# 10_USB.net
KiCad netlist of a schematic drawn in Altium Designer
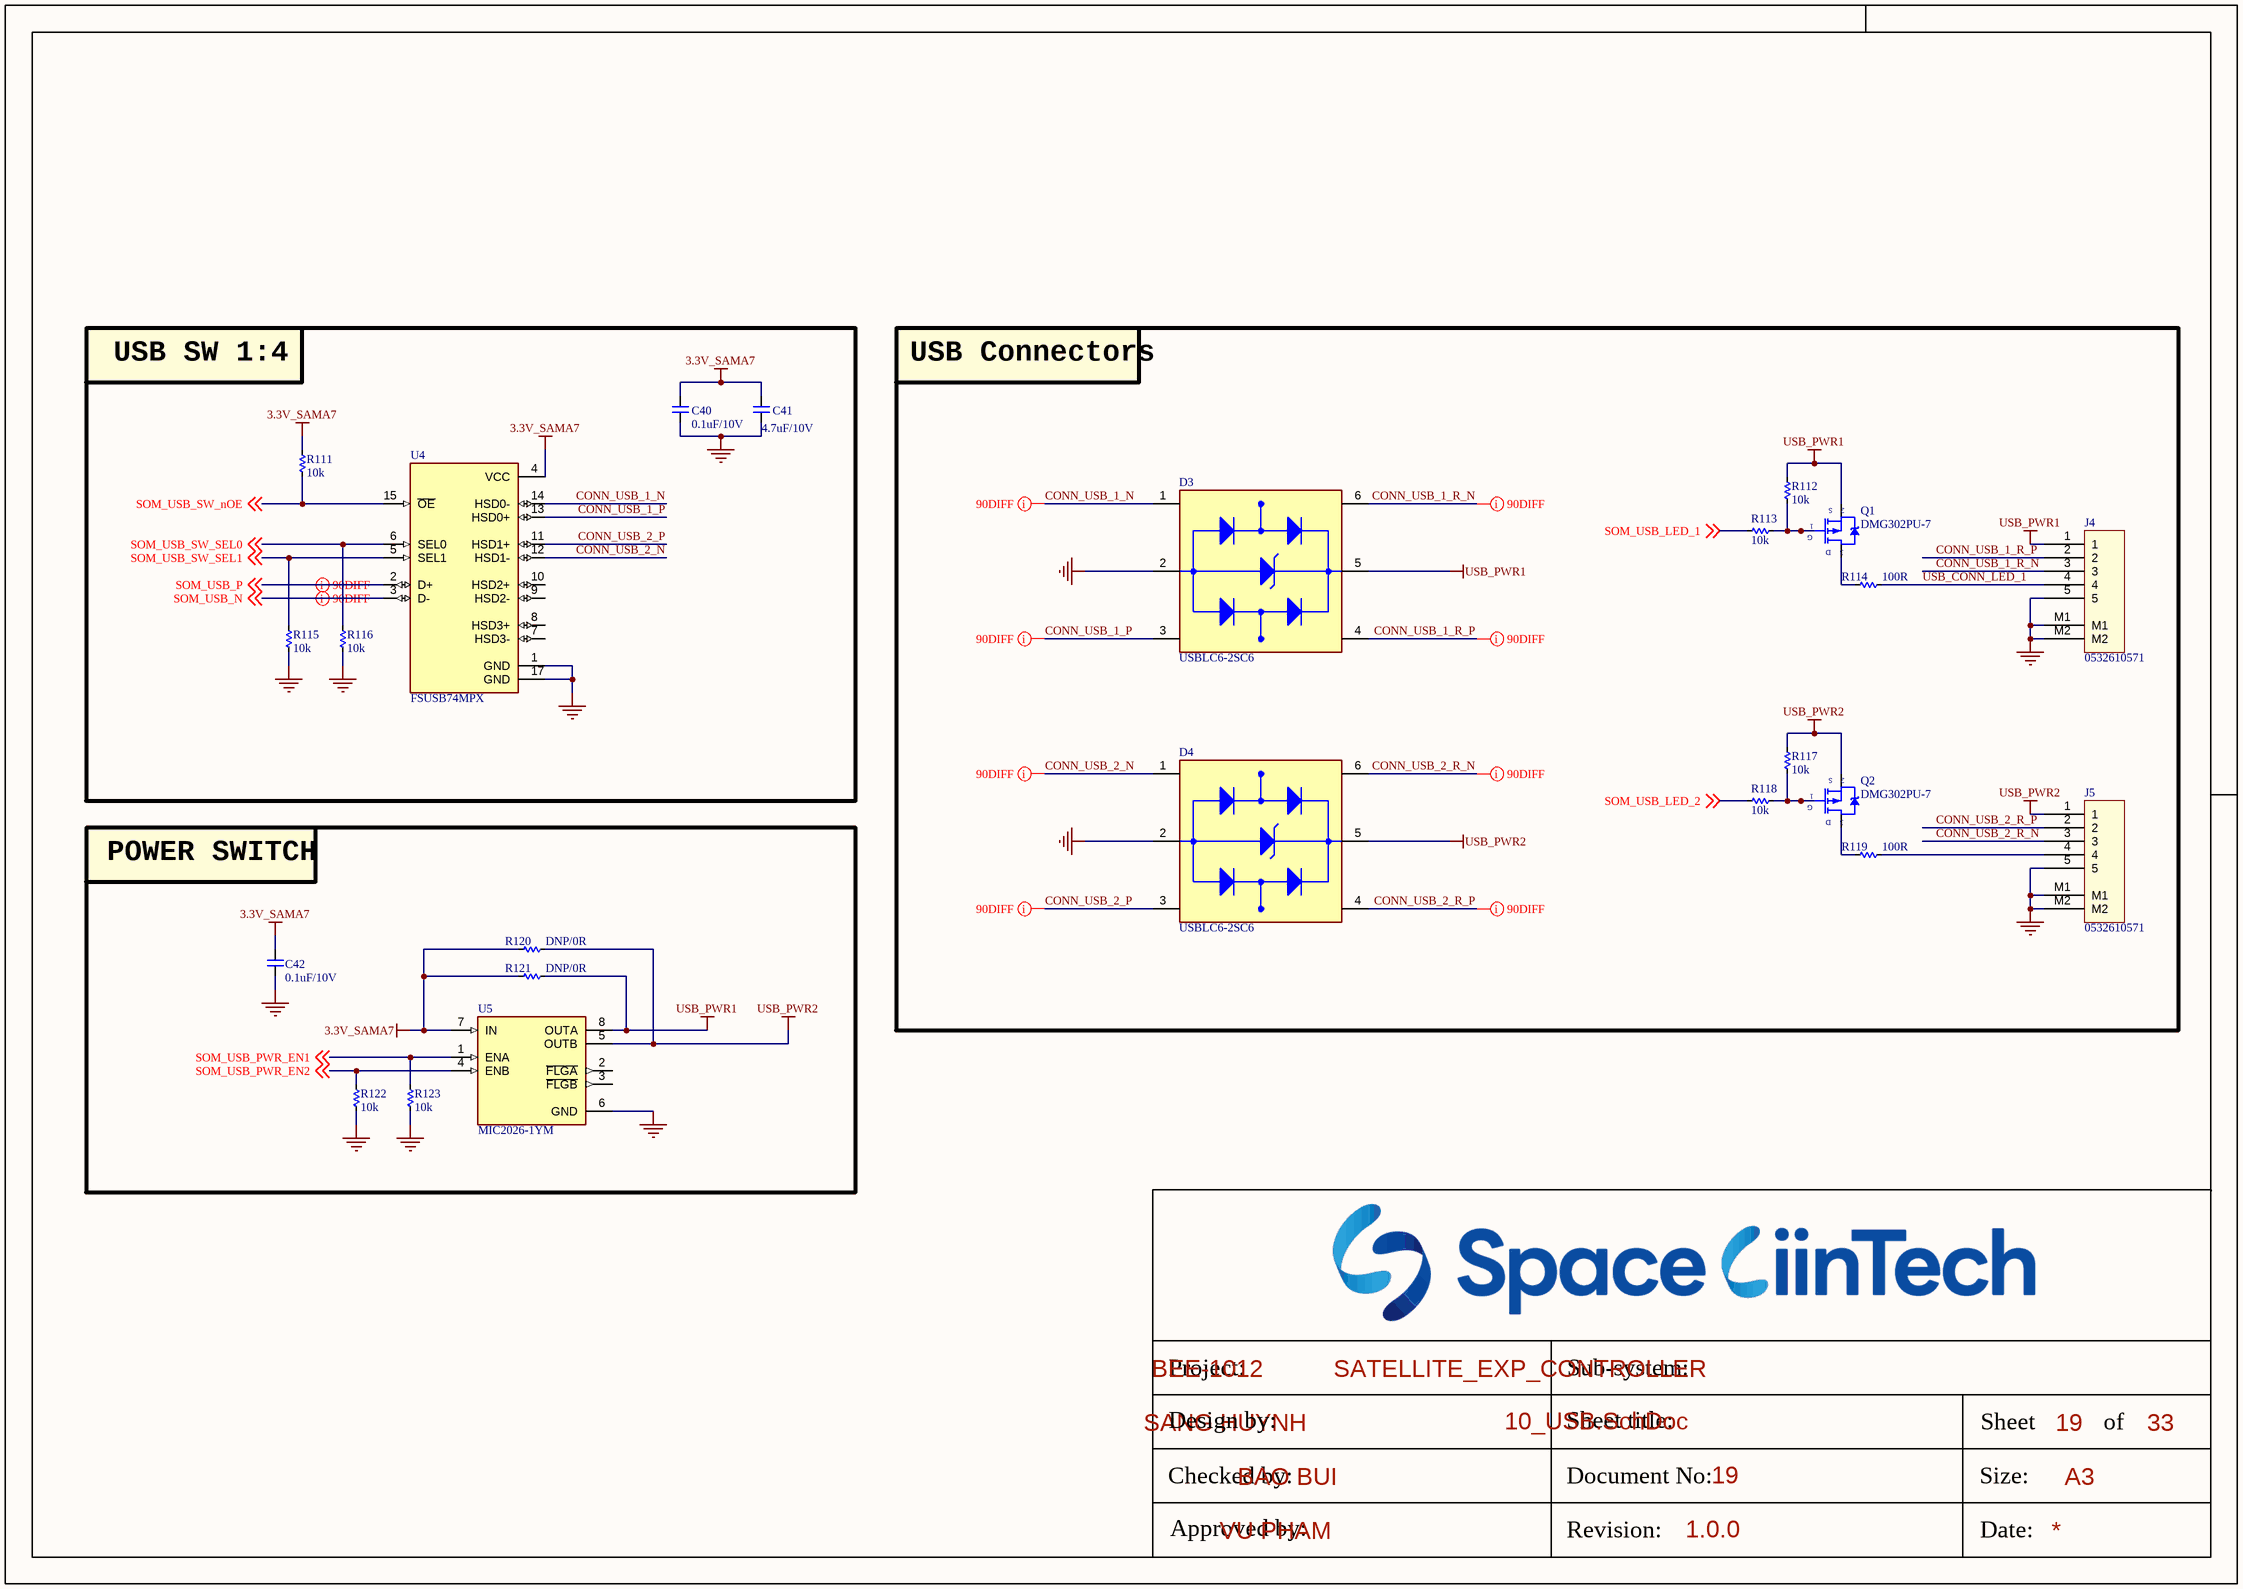
[diagram p0: 10_USB.SchDoc]

(export (version "E")
  (design (tool "Eeschema 10.0.6"))
  (components
    (comp (ref "C40")
      (value "0.1uF/10V")
      (footprint "CAP_C_1005X50_L")
      (description "CAP")
      (libsource (lib "LABLIB") (part "_CAP_C_2"))
    )
    (comp (ref "C41")
      (value "4.7uF/10V")
      (footprint "CAP_C_1005X50_L")
      (description "CAP")
      (libsource (lib "LABLIB") (part "_CAP_C_2"))
    )
    (comp (ref "C42")
      (value "0.1uF/10V")
      (footprint "CAP_C_1005X50_L")
      (description "CAP")
      (libsource (lib "LABLIB") (part "_CAP_C_2"))
    )
    (comp (ref "D3")
      (value "USBLC6-2SC6")
      (footprint "SOT95P280X145-6N")
      (description "17V Clamp 5A (8/20Âµs) Ipp Tvs Diode Surface Mount SOT-23-6")
      (fields (field (name "MF") "STMicroelectronics"))
      (libsource (lib "USBLC6-2SC6") (part "USBLC6-2SC6"))
    )
    (comp (ref "D4")
      (value "USBLC6-2SC6")
      (footprint "SOT95P280X145-6N")
      (description "17V Clamp 5A (8/20Âµs) Ipp Tvs Diode Surface Mount SOT-23-6")
      (fields (field (name "MF") "STMicroelectronics"))
      (libsource (lib "USBLC6-2SC6") (part "USBLC6-2SC6"))
    )
    (comp (ref "J4")
      (value "0532610571")
      (footprint "MOLEX_0532610571")
      (libsource (lib "LABLIB") (part "Header 5x1_2M"))
    )
    (comp (ref "J5")
      (value "0532610571")
      (footprint "MOLEX_0532610571")
      (libsource (lib "LABLIB") (part "Header 5x1_2M"))
    )
    (comp (ref "Q1")
      (value "DMG302PU-7")
      (footprint "SOT95P240X120-3N")
      (libsource (lib "LABLIB") (part "MOSFET_P_GSD"))
    )
    (comp (ref "Q2")
      (value "DMG302PU-7")
      (footprint "SOT95P240X120-3N")
      (libsource (lib "LABLIB") (part "MOSFET_P_GSD"))
    )
    (comp (ref "R111")
      (value "10k")
      (footprint "RES_C_1005x30_L")
      (description "RES")
      (libsource (lib "LABLIB") (part "_RES_B_2"))
    )
    (comp (ref "R112")
      (value "10k")
      (footprint "RES_C_1005x30_L")
      (description "RES")
      (libsource (lib "LABLIB") (part "_RES_B_2"))
    )
    (comp (ref "R113")
      (value "10k")
      (footprint "RES_C_1005x30_L")
      (description "RES")
      (libsource (lib "LABLIB") (part "_RES_B_2"))
    )
    (comp (ref "R114")
      (value "100R")
      (footprint "RES_C_1005x30_L")
      (description "RES")
      (libsource (lib "LABLIB") (part "_RES_B_2"))
    )
    (comp (ref "R115")
      (value "10k")
      (footprint "RES_C_1005x30_L")
      (description "RES")
      (libsource (lib "LABLIB") (part "_RES_B_2"))
    )
    (comp (ref "R116")
      (value "10k")
      (footprint "RES_C_1005x30_L")
      (description "RES")
      (libsource (lib "LABLIB") (part "_RES_B_2"))
    )
    (comp (ref "R117")
      (value "10k")
      (footprint "RES_C_1005x30_L")
      (description "RES")
      (libsource (lib "LABLIB") (part "_RES_B_2"))
    )
    (comp (ref "R118")
      (value "10k")
      (footprint "RES_C_1005x30_L")
      (description "RES")
      (libsource (lib "LABLIB") (part "_RES_B_2"))
    )
    (comp (ref "R119")
      (value "100R")
      (footprint "RES_C_1005x30_L")
      (description "RES")
      (libsource (lib "LABLIB") (part "_RES_B_2"))
    )
    (comp (ref "R120")
      (value "DNP/0R")
      (footprint "RES_C_1005x30_L")
      (description "RES")
      (libsource (lib "LABLIB") (part "_RES_B_2"))
    )
    (comp (ref "R121")
      (value "DNP/0R")
      (footprint "RES_C_1005x30_L")
      (description "RES")
      (libsource (lib "LABLIB") (part "_RES_B_2"))
    )
    (comp (ref "R122")
      (value "10k")
      (footprint "RES_C_1005x30_L")
      (description "RES")
      (libsource (lib "LABLIB") (part "_RES_B_2"))
    )
    (comp (ref "R123")
      (value "10k")
      (footprint "RES_C_1005x30_L")
      (description "RES")
      (libsource (lib "LABLIB") (part "_RES_B_2"))
    )
    (comp (ref "U4")
      (value "FSUSB74MPX")
      (footprint "QFN50P300X300X80-17N")
      (description "USB Switch IC 1 Channel 16-MLP (3x3)")
      (fields (field (name "MF") "ON Semiconductor"))
      (libsource (lib "LABLIB") (part "IC_USB_SW_FSUSB74MPX"))
    )
    (comp (ref "U5")
      (value "MIC2026-1YM")
      (footprint "SOIC127P602X173-8N")
      (description "Power Switch/Driver 1:2 N-Channel 1.25A 8-SOIC")
      (fields (field (name "MF") "Microchip"))
      (libsource (lib "LABLIB") (part "IC_PWRSW_MIC2026-1YM"))
    )
  )
  (nets
    (net (code "1") (name "/CONN_USB_1_N") (class "Default")
      (node (ref "D3") (pin "1") (pinfunction "I/O1_IN_1") (pintype "passive"))
      (node (ref "U4") (pin "14") (pinfunction "HSD0-_14") (pintype "bidirectional"))
    )
    (net (code "2") (name "/CONN_USB_1_P") (class "Default")
      (node (ref "D3") (pin "3") (pinfunction "I/O2_IN_3") (pintype "passive"))
      (node (ref "U4") (pin "13") (pinfunction "HSD0+_13") (pintype "bidirectional"))
    )
    (net (code "3") (name "/CONN_USB_1_R_N") (class "Default")
      (node (ref "D3") (pin "6") (pinfunction "I/O1_OUT_6") (pintype "passive"))
      (node (ref "J4") (pin "3") (pinfunction "3_3") (pintype "passive"))
    )
    (net (code "4") (name "/CONN_USB_1_R_P") (class "Default")
      (node (ref "D3") (pin "4") (pinfunction "I/O2_OUT_4") (pintype "passive"))
      (node (ref "J4") (pin "2") (pinfunction "2_2") (pintype "passive"))
    )
    (net (code "5") (name "/CONN_USB_2_N") (class "Default")
      (node (ref "D4") (pin "1") (pinfunction "I/O1_IN_1") (pintype "passive"))
      (node (ref "U4") (pin "12") (pinfunction "HSD1-_12") (pintype "bidirectional"))
    )
    (net (code "6") (name "/CONN_USB_2_P") (class "Default")
      (node (ref "D4") (pin "3") (pinfunction "I/O2_IN_3") (pintype "passive"))
      (node (ref "U4") (pin "11") (pinfunction "HSD1+_11") (pintype "bidirectional"))
    )
    (net (code "7") (name "/CONN_USB_2_R_N") (class "Default")
      (node (ref "D4") (pin "6") (pinfunction "I/O1_OUT_6") (pintype "passive"))
      (node (ref "J5") (pin "3") (pinfunction "3_3") (pintype "passive"))
    )
    (net (code "8") (name "/CONN_USB_2_R_P") (class "Default")
      (node (ref "D4") (pin "4") (pinfunction "I/O2_OUT_4") (pintype "passive"))
      (node (ref "J5") (pin "2") (pinfunction "2_2") (pintype "passive"))
    )
    (net (code "9") (name "/USB_CONN_LED_1") (class "Default")
      (node (ref "J4") (pin "4") (pinfunction "4_4") (pintype "passive"))
      (node (ref "R114") (pin "2") (pinfunction "2_2") (pintype "passive"))
    )
    (net (code "10") (name "3.3V_SAMA7") (class "Default")
      (node (ref "C40") (pin "2") (pinfunction "2_2") (pintype "passive"))
      (node (ref "C41") (pin "2") (pinfunction "2_2") (pintype "passive"))
      (node (ref "C42") (pin "2") (pinfunction "2_2") (pintype "passive"))
      (node (ref "R111") (pin "1") (pinfunction "1_1") (pintype "passive"))
      (node (ref "R120") (pin "2") (pinfunction "2_2") (pintype "passive"))
      (node (ref "R121") (pin "2") (pinfunction "2_2") (pintype "passive"))
      (node (ref "U4") (pin "4") (pinfunction "VCC_4") (pintype "power_in"))
      (node (ref "U5") (pin "7") (pinfunction "IN_7") (pintype "input"))
    )
    (net (code "11") (name "GND") (class "Default")
      (node (ref "C40") (pin "1") (pinfunction "1_1") (pintype "passive"))
      (node (ref "C41") (pin "1") (pinfunction "1_1") (pintype "passive"))
      (node (ref "C42") (pin "1") (pinfunction "1_1") (pintype "passive"))
      (node (ref "D3") (pin "2") (pinfunction "GND_2") (pintype "power_in"))
      (node (ref "D4") (pin "2") (pinfunction "GND_2") (pintype "power_in"))
      (node (ref "J4") (pin "5") (pinfunction "5_5") (pintype "passive"))
      (node (ref "J4") (pin "M1") (pinfunction "M1_M1") (pintype "passive"))
      (node (ref "J4") (pin "M2") (pinfunction "M2_M2") (pintype "passive"))
      (node (ref "J5") (pin "5") (pinfunction "5_5") (pintype "passive"))
      (node (ref "J5") (pin "M1") (pinfunction "M1_M1") (pintype "passive"))
      (node (ref "J5") (pin "M2") (pinfunction "M2_M2") (pintype "passive"))
      (node (ref "R115") (pin "2") (pinfunction "2_2") (pintype "passive"))
      (node (ref "R116") (pin "2") (pinfunction "2_2") (pintype "passive"))
      (node (ref "R122") (pin "2") (pinfunction "2_2") (pintype "passive"))
      (node (ref "R123") (pin "2") (pinfunction "2_2") (pintype "passive"))
      (node (ref "U4") (pin "1") (pinfunction "GND_1") (pintype "power_in"))
      (node (ref "U4") (pin "17") (pinfunction "GND_17") (pintype "power_in"))
      (node (ref "U5") (pin "6") (pinfunction "GND_6") (pintype "power_in"))
    )
    (net (code "12") (name "Net-(J5-Pad4)") (class "Default")
      (node (ref "J5") (pin "4") (pinfunction "4_4") (pintype "passive"))
      (node (ref "R119") (pin "2") (pinfunction "2_2") (pintype "passive"))
    )
    (net (code "13") (name "Net-(Q1-D)") (class "Default")
      (node (ref "Q1") (pin "3") (pinfunction "D_3") (pintype "passive"))
      (node (ref "R114") (pin "1") (pinfunction "1_1") (pintype "passive"))
    )
    (net (code "14") (name "Net-(Q1-G)") (class "Default")
      (node (ref "Q1") (pin "1") (pinfunction "G_1") (pintype "passive"))
      (node (ref "R112") (pin "2") (pinfunction "2_2") (pintype "passive"))
      (node (ref "R113") (pin "2") (pinfunction "2_2") (pintype "passive"))
    )
    (net (code "15") (name "Net-(Q2-D)") (class "Default")
      (node (ref "Q2") (pin "3") (pinfunction "D_3") (pintype "passive"))
      (node (ref "R119") (pin "1") (pinfunction "1_1") (pintype "passive"))
    )
    (net (code "16") (name "Net-(Q2-G)") (class "Default")
      (node (ref "Q2") (pin "1") (pinfunction "G_1") (pintype "passive"))
      (node (ref "R117") (pin "2") (pinfunction "2_2") (pintype "passive"))
      (node (ref "R118") (pin "2") (pinfunction "2_2") (pintype "passive"))
    )
    (net (code "17") (name "SOM_USB_LED_1") (class "Default")
      (node (ref "R113") (pin "1") (pinfunction "1_1") (pintype "passive"))
    )
    (net (code "18") (name "SOM_USB_LED_2") (class "Default")
      (node (ref "R118") (pin "1") (pinfunction "1_1") (pintype "passive"))
    )
    (net (code "19") (name "SOM_USB_N") (class "Default")
      (node (ref "U4") (pin "3") (pinfunction "D-_3") (pintype "bidirectional"))
    )
    (net (code "20") (name "SOM_USB_P") (class "Default")
      (node (ref "U4") (pin "2") (pinfunction "D+_2") (pintype "bidirectional"))
    )
    (net (code "21") (name "SOM_USB_PWR_EN1") (class "Default")
      (node (ref "R123") (pin "1") (pinfunction "1_1") (pintype "passive"))
      (node (ref "U5") (pin "1") (pinfunction "ENA_1") (pintype "input"))
    )
    (net (code "22") (name "SOM_USB_PWR_EN2") (class "Default")
      (node (ref "R122") (pin "1") (pinfunction "1_1") (pintype "passive"))
      (node (ref "U5") (pin "4") (pinfunction "ENB_4") (pintype "input"))
    )
    (net (code "23") (name "SOM_USB_SW_SEL0") (class "Default")
      (node (ref "R116") (pin "1") (pinfunction "1_1") (pintype "passive"))
      (node (ref "U4") (pin "6") (pinfunction "SEL0_6") (pintype "input"))
    )
    (net (code "24") (name "SOM_USB_SW_SEL1") (class "Default")
      (node (ref "R115") (pin "1") (pinfunction "1_1") (pintype "passive"))
      (node (ref "U4") (pin "5") (pinfunction "SEL1_5") (pintype "input"))
    )
    (net (code "25") (name "SOM_USB_SW_nOE") (class "Default")
      (node (ref "R111") (pin "2") (pinfunction "2_2") (pintype "passive"))
      (node (ref "U4") (pin "15") (pinfunction "~{OE}_15") (pintype "input"))
    )
    (net (code "26") (name "USB_PWR1") (class "Default")
      (node (ref "D3") (pin "5") (pinfunction "VBUS_5") (pintype "power_in"))
      (node (ref "J4") (pin "1") (pinfunction "1_1") (pintype "passive"))
      (node (ref "Q1") (pin "2") (pinfunction "S_2") (pintype "passive"))
      (node (ref "R112") (pin "1") (pinfunction "1_1") (pintype "passive"))
      (node (ref "R121") (pin "1") (pinfunction "1_1") (pintype "passive"))
      (node (ref "U5") (pin "8") (pinfunction "OUTA_8") (pintype "passive"))
    )
    (net (code "27") (name "USB_PWR2") (class "Default")
      (node (ref "D4") (pin "5") (pinfunction "VBUS_5") (pintype "power_in"))
      (node (ref "J5") (pin "1") (pinfunction "1_1") (pintype "passive"))
      (node (ref "Q2") (pin "2") (pinfunction "S_2") (pintype "passive"))
      (node (ref "R117") (pin "1") (pinfunction "1_1") (pintype "passive"))
      (node (ref "R120") (pin "1") (pinfunction "1_1") (pintype "passive"))
      (node (ref "U5") (pin "5") (pinfunction "OUTB_5") (pintype "passive"))
    )
    (net (code "28") (name "unconnected-(U4-HSD2+-Pad10)") (class "Default")
      (node (ref "U4") (pin "10") (pinfunction "HSD2+_10") (pintype "bidirectional"))
    )
    (net (code "29") (name "unconnected-(U4-HSD2--Pad9)") (class "Default")
      (node (ref "U4") (pin "9") (pinfunction "HSD2-_9") (pintype "bidirectional"))
    )
    (net (code "30") (name "unconnected-(U4-HSD3+-Pad8)") (class "Default")
      (node (ref "U4") (pin "8") (pinfunction "HSD3+_8") (pintype "bidirectional"))
    )
    (net (code "31") (name "unconnected-(U4-HSD3--Pad7)") (class "Default")
      (node (ref "U4") (pin "7") (pinfunction "HSD3-_7") (pintype "bidirectional"))
    )
    (net (code "32") (name "unconnected-(U5-~{FLGA}-Pad2)") (class "Default")
      (node (ref "U5") (pin "2") (pinfunction "~{FLGA}_2") (pintype "output"))
    )
    (net (code "33") (name "unconnected-(U5-~{FLGB}-Pad3)") (class "Default")
      (node (ref "U5") (pin "3") (pinfunction "~{FLGB}_3") (pintype "output"))
    )
  )
)
